# Res_Cut.net
KiCad netlist of a schematic drawn in EAGLE
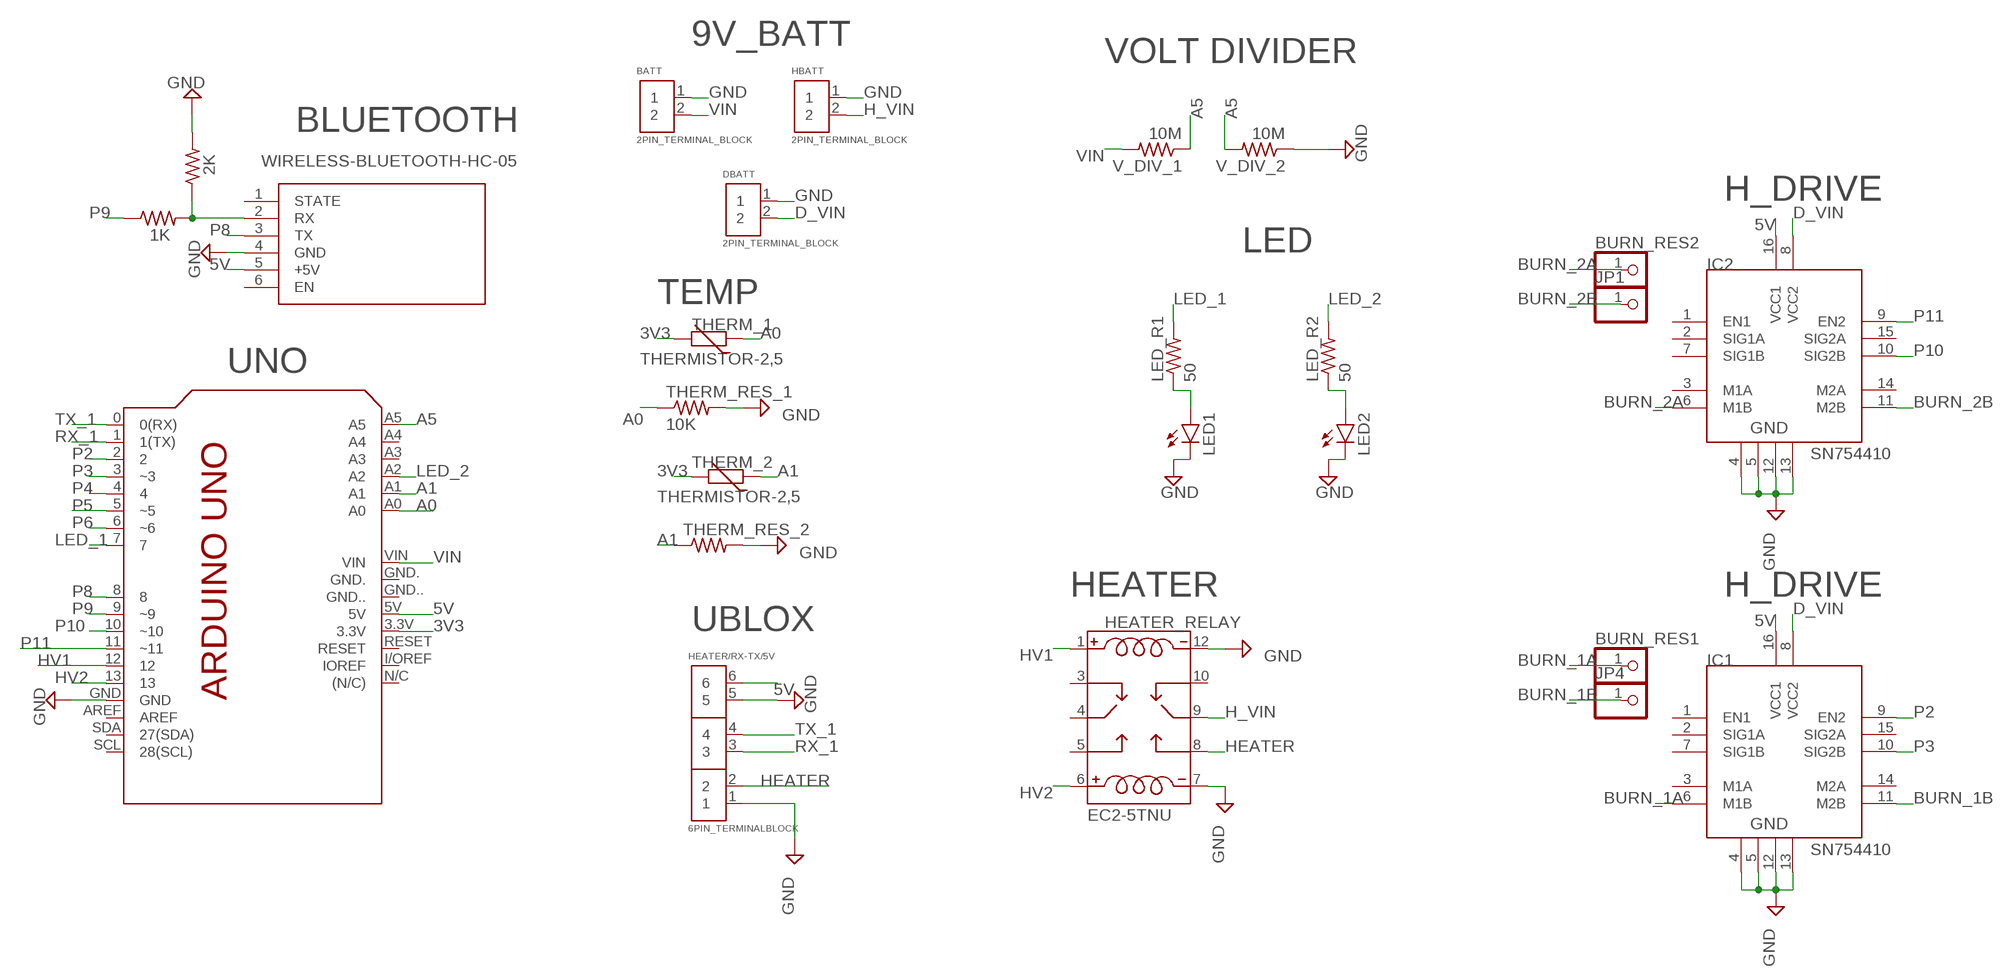
[diagram p0: schematic, sheet 1]

(export (version "E")
  (design (tool "Eeschema 10.0.6"))
  (components
    (comp (ref "BATT")
      (value "2PIN_TERMINAL_BLOCK")
      (footprint "eagle-import:2PIN_TERMINAL_BLOCK")
      (fields
        (field (name "COMMENT") "282834-2")
        (field (name "DIGI-KEY_PART_NUMBER") "A98333-ND")
        (field (name "MF") "TE Connectivity")
      )
      (libsource (lib "eagle-import") (part "2PIN_TERMINAL_BLOCK"))
    )
    (comp (ref "BLUE_R1")
      (value "1K")
      (footprint "eagle-import:0204_7")
      (libsource (lib "eagle-import") (part "R-US_0204/7"))
    )
    (comp (ref "BLUE_R2")
      (value "2K")
      (footprint "eagle-import:0204_7")
      (libsource (lib "eagle-import") (part "R-US_0204/7"))
    )
    (comp (ref "BURN_RES1")
      (value "PINHD-1X1CB")
      (footprint "eagle-import:1X01-CLEANBIG")
      (libsource (lib "eagle-import") (part "PINHD-1X1CB"))
    )
    (comp (ref "BURN_RES2")
      (value "PINHD-1X1CB")
      (footprint "eagle-import:1X01-CLEANBIG")
      (libsource (lib "eagle-import") (part "PINHD-1X1CB"))
    )
    (comp (ref "DBATT")
      (value "2PIN_TERMINAL_BLOCK")
      (footprint "eagle-import:2PIN_TERMINAL_BLOCK")
      (fields
        (field (name "COMMENT") "282834-2")
        (field (name "DIGI-KEY_PART_NUMBER") "A98333-ND")
        (field (name "MF") "TE Connectivity")
      )
      (libsource (lib "eagle-import") (part "2PIN_TERMINAL_BLOCK"))
    )
    (comp (ref "HBATT")
      (value "2PIN_TERMINAL_BLOCK")
      (footprint "eagle-import:2PIN_TERMINAL_BLOCK")
      (fields
        (field (name "COMMENT") "282834-2")
        (field (name "DIGI-KEY_PART_NUMBER") "A98333-ND")
        (field (name "MF") "TE Connectivity")
      )
      (libsource (lib "eagle-import") (part "2PIN_TERMINAL_BLOCK"))
    )
    (comp (ref "HEATER/RX-TX/5V")
      (value "6PIN_TERMINALBLOCK")
      (footprint "eagle-import:6PIN_TERMINALBLOCK")
      (libsource (lib "eagle-import") (part "6PIN_TERMINALBLOCK"))
    )
    (comp (ref "HEATER_RELAY")
      (value "EC2-5TNU")
      (footprint "eagle-import:RELAY_EC2-5TNU")
      (fields (field (name "MF") "KEMET"))
      (libsource (lib "eagle-import") (part "EC2-5TNU"))
    )
    (comp (ref "IC1")
      (value "SN754410")
      (footprint "eagle-import:DIP16")
      (libsource (lib "eagle-import") (part "SN754410"))
    )
    (comp (ref "IC2")
      (value "SN754410")
      (footprint "eagle-import:DIP16")
      (libsource (lib "eagle-import") (part "SN754410"))
    )
    (comp (ref "JP1")
      (value "PINHD-1X1CB")
      (footprint "eagle-import:1X01-CLEANBIG")
      (libsource (lib "eagle-import") (part "PINHD-1X1CB"))
    )
    (comp (ref "JP4")
      (value "PINHD-1X1CB")
      (footprint "eagle-import:1X01-CLEANBIG")
      (libsource (lib "eagle-import") (part "PINHD-1X1CB"))
    )
    (comp (ref "LED1")
      (value "TLLR4400")
      (footprint "eagle-import:LED3MM")
      (fields (field (name "MF") "VISHAY SEMICONDUCTOR"))
      (libsource (lib "eagle-import") (part "TLLR4400"))
    )
    (comp (ref "LED2")
      (value "TLLR4400")
      (footprint "eagle-import:LED3MM")
      (fields (field (name "MF") "VISHAY SEMICONDUCTOR"))
      (libsource (lib "eagle-import") (part "TLLR4400"))
    )
    (comp (ref "LED_R1")
      (value "50")
      (footprint "eagle-import:0204_7")
      (libsource (lib "eagle-import") (part "resistor_348_R-US_0204/7"))
    )
    (comp (ref "LED_R2")
      (value "50")
      (footprint "eagle-import:0204_7")
      (libsource (lib "eagle-import") (part "resistor_348_R-US_0204/7"))
    )
    (comp (ref "PCB1")
      (value "ARDUINO_UNO")
      (footprint "eagle-import:ARDUINO_UNO")
      (libsource (lib "eagle-import") (part "ARDUINO_UNO"))
    )
    (comp (ref "THERM_1")
      (value "THERMISTOR-2,5")
      (footprint "eagle-import:RS-2,5")
      (libsource (lib "eagle-import") (part "THERMISTOR-2,5"))
    )
    (comp (ref "THERM_2")
      (value "THERMISTOR-2,5")
      (footprint "eagle-import:RS-2,5")
      (libsource (lib "eagle-import") (part "THERMISTOR-2,5"))
    )
    (comp (ref "THERM_RES_1")
      (value "10K")
      (footprint "eagle-import:0204_7")
      (libsource (lib "eagle-import") (part "R-US_0204/7"))
    )
    (comp (ref "THERM_RES_2")
      (value "10K")
      (footprint "eagle-import:0204_7")
      (libsource (lib "eagle-import") (part "R-US_0204/7"))
    )
    (comp (ref "U$1")
      (value "WIRELESS-BLUETOOTH-HC-05")
      (footprint "eagle-import:WIRELESS-BLUETOOTH-HC-05")
      (libsource (lib "eagle-import") (part "WIRELESS-BLUETOOTH-HC-05"))
    )
    (comp (ref "V_DIV_1")
      (value "10M")
      (footprint "eagle-import:0204_7")
      (libsource (lib "eagle-import") (part "resistor_348_R-US_0204/7"))
    )
    (comp (ref "V_DIV_2")
      (value "10M")
      (footprint "eagle-import:0204_7")
      (libsource (lib "eagle-import") (part "resistor_348_R-US_0204/7"))
    )
  )
  (nets
    (net (code "1") (name "/3V3") (class "Default")
      (node (ref "PCB1") (pin "3.3V") (pinfunction "3.3V_3.3V") (pintype "bidirectional"))
      (node (ref "THERM_1") (pin "2") (pinfunction "2_2") (pintype "passive"))
      (node (ref "THERM_2") (pin "2") (pinfunction "2_2") (pintype "passive"))
    )
    (net (code "2") (name "/5V") (class "Default")
      (node (ref "HEATER/RX-TX/5V") (pin "6") (pinfunction "6_6") (pintype "passive"))
      (node (ref "IC1") (pin "16") (pinfunction "VCC1_16") (pintype "power_in"))
      (node (ref "IC2") (pin "16") (pinfunction "VCC1_16") (pintype "power_in"))
      (node (ref "PCB1") (pin "5V") (pinfunction "5V_5V") (pintype "bidirectional"))
      (node (ref "U$1") (pin "5") (pinfunction "+5V_5") (pintype "power_in"))
    )
    (net (code "3") (name "/A0") (class "Default")
      (node (ref "PCB1") (pin "A0") (pinfunction "A0_A0") (pintype "bidirectional"))
      (node (ref "THERM_1") (pin "1") (pinfunction "1_1") (pintype "passive"))
      (node (ref "THERM_RES_1") (pin "1") (pinfunction "1_1") (pintype "passive"))
    )
    (net (code "4") (name "/A1") (class "Default")
      (node (ref "PCB1") (pin "A1") (pinfunction "A1_A1") (pintype "bidirectional"))
      (node (ref "THERM_2") (pin "1") (pinfunction "1_1") (pintype "passive"))
      (node (ref "THERM_RES_2") (pin "1") (pinfunction "1_1") (pintype "passive"))
    )
    (net (code "5") (name "/A5") (class "Default")
      (node (ref "PCB1") (pin "A5") (pinfunction "A5_A5") (pintype "bidirectional"))
      (node (ref "V_DIV_1") (pin "1") (pinfunction "1_1") (pintype "passive"))
      (node (ref "V_DIV_2") (pin "2") (pinfunction "2_2") (pintype "passive"))
    )
    (net (code "6") (name "/BURN_1A") (class "Default")
      (node (ref "BURN_RES1") (pin "1") (pinfunction "1_1") (pintype "passive"))
      (node (ref "IC1") (pin "6") (pinfunction "M1B_6") (pintype "bidirectional"))
    )
    (net (code "7") (name "/BURN_1B") (class "Default")
      (node (ref "IC1") (pin "11") (pinfunction "M2B_11") (pintype "bidirectional"))
      (node (ref "JP4") (pin "1") (pinfunction "1_1") (pintype "passive"))
    )
    (net (code "8") (name "/BURN_2A") (class "Default")
      (node (ref "BURN_RES2") (pin "1") (pinfunction "1_1") (pintype "passive"))
      (node (ref "IC2") (pin "6") (pinfunction "M1B_6") (pintype "bidirectional"))
    )
    (net (code "9") (name "/BURN_2B") (class "Default")
      (node (ref "IC2") (pin "11") (pinfunction "M2B_11") (pintype "bidirectional"))
      (node (ref "JP1") (pin "1") (pinfunction "1_1") (pintype "passive"))
    )
    (net (code "10") (name "/D_VIN") (class "Default")
      (node (ref "DBATT") (pin "2") (pinfunction "2_2") (pintype "passive"))
      (node (ref "IC1") (pin "8") (pinfunction "VCC2_8") (pintype "power_in"))
      (node (ref "IC2") (pin "8") (pinfunction "VCC2_8") (pintype "power_in"))
    )
    (net (code "11") (name "/HEATER") (class "Default")
      (node (ref "HEATER/RX-TX/5V") (pin "2") (pinfunction "2_2") (pintype "passive"))
      (node (ref "HEATER_RELAY") (pin "8") (pinfunction "NO_8") (pintype "passive"))
    )
    (net (code "12") (name "/HV1") (class "Default")
      (node (ref "HEATER_RELAY") (pin "1") (pinfunction "C1_1") (pintype "passive"))
      (node (ref "PCB1") (pin "12") (pinfunction "12_12") (pintype "bidirectional"))
    )
    (net (code "13") (name "/HV2") (class "Default")
      (node (ref "HEATER_RELAY") (pin "6") (pinfunction "C3_6") (pintype "passive"))
      (node (ref "PCB1") (pin "13") (pinfunction "13_13") (pintype "bidirectional"))
    )
    (net (code "14") (name "/H_VIN") (class "Default")
      (node (ref "HBATT") (pin "2") (pinfunction "2_2") (pintype "passive"))
      (node (ref "HEATER_RELAY") (pin "9") (pinfunction "M_9") (pintype "passive"))
    )
    (net (code "15") (name "/LED_1") (class "Default")
      (node (ref "LED_R1") (pin "2") (pinfunction "2_2") (pintype "passive"))
      (node (ref "PCB1") (pin "7") (pinfunction "7_7") (pintype "bidirectional"))
    )
    (net (code "16") (name "/LED_2") (class "Default")
      (node (ref "LED_R2") (pin "2") (pinfunction "2_2") (pintype "passive"))
      (node (ref "PCB1") (pin "A2") (pinfunction "A2_A2") (pintype "bidirectional"))
    )
    (net (code "17") (name "/P2") (class "Default")
      (node (ref "IC1") (pin "9") (pinfunction "EN2_9") (pintype "bidirectional"))
      (node (ref "PCB1") (pin "2") (pinfunction "2_2") (pintype "bidirectional"))
    )
    (net (code "18") (name "/P3") (class "Default")
      (node (ref "IC1") (pin "10") (pinfunction "SIG2B_10") (pintype "bidirectional"))
      (node (ref "PCB1") (pin "3") (pinfunction "~{3}_3") (pintype "bidirectional"))
    )
    (net (code "19") (name "/P4") (class "Default")
      (node (ref "PCB1") (pin "4") (pinfunction "4_4") (pintype "bidirectional"))
    )
    (net (code "20") (name "/P5") (class "Default")
      (node (ref "PCB1") (pin "5") (pinfunction "~{5}_5") (pintype "bidirectional"))
    )
    (net (code "21") (name "/P6") (class "Default")
      (node (ref "PCB1") (pin "6") (pinfunction "~{6}_6") (pintype "bidirectional"))
    )
    (net (code "22") (name "/P8") (class "Default")
      (node (ref "PCB1") (pin "8") (pinfunction "8_8") (pintype "bidirectional"))
      (node (ref "U$1") (pin "3") (pinfunction "TX_3") (pintype "bidirectional"))
    )
    (net (code "23") (name "/P9") (class "Default")
      (node (ref "BLUE_R1") (pin "1") (pinfunction "1_1") (pintype "passive"))
      (node (ref "PCB1") (pin "9") (pinfunction "~{9}_9") (pintype "bidirectional"))
    )
    (net (code "24") (name "/P10") (class "Default")
      (node (ref "IC2") (pin "10") (pinfunction "SIG2B_10") (pintype "bidirectional"))
      (node (ref "PCB1") (pin "10") (pinfunction "~{10}_10") (pintype "bidirectional"))
    )
    (net (code "25") (name "/P11") (class "Default")
      (node (ref "IC2") (pin "9") (pinfunction "EN2_9") (pintype "bidirectional"))
      (node (ref "PCB1") (pin "11") (pinfunction "~{11}_11") (pintype "bidirectional"))
    )
    (net (code "26") (name "/RX_1") (class "Default")
      (node (ref "HEATER/RX-TX/5V") (pin "3") (pinfunction "3_3") (pintype "passive"))
      (node (ref "PCB1") (pin "1") (pinfunction "1(TX)_1") (pintype "bidirectional"))
    )
    (net (code "27") (name "/TX_1") (class "Default")
      (node (ref "HEATER/RX-TX/5V") (pin "4") (pinfunction "4_4") (pintype "passive"))
      (node (ref "PCB1") (pin "0") (pinfunction "0(RX)_0") (pintype "bidirectional"))
    )
    (net (code "28") (name "/VIN") (class "Default")
      (node (ref "BATT") (pin "2") (pinfunction "2_2") (pintype "passive"))
      (node (ref "PCB1") (pin "VIN") (pinfunction "VIN_VIN") (pintype "bidirectional"))
      (node (ref "V_DIV_1") (pin "2") (pinfunction "2_2") (pintype "passive"))
    )
    (net (code "29") (name "GND") (class "Default")
      (node (ref "BATT") (pin "1") (pinfunction "1_1") (pintype "passive"))
      (node (ref "BLUE_R2") (pin "2") (pinfunction "2_2") (pintype "passive"))
      (node (ref "DBATT") (pin "1") (pinfunction "1_1") (pintype "passive"))
      (node (ref "HBATT") (pin "1") (pinfunction "1_1") (pintype "passive"))
      (node (ref "HEATER/RX-TX/5V") (pin "1") (pinfunction "1_1") (pintype "passive"))
      (node (ref "HEATER/RX-TX/5V") (pin "5") (pinfunction "5_5") (pintype "passive"))
      (node (ref "HEATER_RELAY") (pin "12") (pinfunction "C2_12") (pintype "passive"))
      (node (ref "HEATER_RELAY") (pin "7") (pinfunction "C4_7") (pintype "passive"))
      (node (ref "IC1") (pin "12") (pinfunction "P12_12") (pintype "power_in"))
      (node (ref "IC1") (pin "13") (pinfunction "P13_13") (pintype "power_in"))
      (node (ref "IC1") (pin "4") (pinfunction "P4_4") (pintype "power_in"))
      (node (ref "IC1") (pin "5") (pinfunction "P5_5") (pintype "power_in"))
      (node (ref "IC2") (pin "12") (pinfunction "P12_12") (pintype "power_in"))
      (node (ref "IC2") (pin "13") (pinfunction "P13_13") (pintype "power_in"))
      (node (ref "IC2") (pin "4") (pinfunction "P4_4") (pintype "power_in"))
      (node (ref "IC2") (pin "5") (pinfunction "P5_5") (pintype "power_in"))
      (node (ref "LED1") (pin "K") (pinfunction "C_K") (pintype "passive"))
      (node (ref "LED2") (pin "K") (pinfunction "C_K") (pintype "passive"))
      (node (ref "PCB1") (pin "GND") (pinfunction "GND_GND") (pintype "bidirectional"))
      (node (ref "THERM_RES_1") (pin "2") (pinfunction "2_2") (pintype "passive"))
      (node (ref "THERM_RES_2") (pin "2") (pinfunction "2_2") (pintype "passive"))
      (node (ref "U$1") (pin "4") (pinfunction "GND_4") (pintype "power_in"))
      (node (ref "V_DIV_2") (pin "1") (pinfunction "1_1") (pintype "passive"))
    )
    (net (code "30") (name "Net-(LED1-PadA)") (class "Default")
      (node (ref "LED1") (pin "A") (pinfunction "A_A") (pintype "passive"))
      (node (ref "LED_R1") (pin "1") (pinfunction "1_1") (pintype "passive"))
    )
    (net (code "31") (name "Net-(LED2-PadA)") (class "Default")
      (node (ref "LED2") (pin "A") (pinfunction "A_A") (pintype "passive"))
      (node (ref "LED_R2") (pin "1") (pinfunction "1_1") (pintype "passive"))
    )
    (net (code "32") (name "Net-(U$1-RX)") (class "Default")
      (node (ref "BLUE_R1") (pin "2") (pinfunction "2_2") (pintype "passive"))
      (node (ref "BLUE_R2") (pin "1") (pinfunction "1_1") (pintype "passive"))
      (node (ref "U$1") (pin "2") (pinfunction "RX_2") (pintype "bidirectional"))
    )
    (net (code "33") (name "unconnected-(HEATER_RELAY-M1-Pad4)") (class "Default")
      (node (ref "HEATER_RELAY") (pin "4") (pinfunction "M1_4") (pintype "passive"))
    )
    (net (code "34") (name "unconnected-(HEATER_RELAY-NC-Pad10)") (class "Default")
      (node (ref "HEATER_RELAY") (pin "10") (pinfunction "NC_10") (pintype "passive"))
    )
    (net (code "35") (name "unconnected-(HEATER_RELAY-NC1-Pad3)") (class "Default")
      (node (ref "HEATER_RELAY") (pin "3") (pinfunction "NC1_3") (pintype "passive"))
    )
    (net (code "36") (name "unconnected-(HEATER_RELAY-NO1-Pad5)") (class "Default")
      (node (ref "HEATER_RELAY") (pin "5") (pinfunction "NO1_5") (pintype "passive"))
    )
    (net (code "37") (name "unconnected-(IC1-EN1-Pad1)") (class "Default")
      (node (ref "IC1") (pin "1") (pinfunction "EN1_1") (pintype "bidirectional"))
    )
    (net (code "38") (name "unconnected-(IC1-M1A-Pad3)") (class "Default")
      (node (ref "IC1") (pin "3") (pinfunction "M1A_3") (pintype "bidirectional"))
    )
    (net (code "39") (name "unconnected-(IC1-M2A-Pad14)") (class "Default")
      (node (ref "IC1") (pin "14") (pinfunction "M2A_14") (pintype "bidirectional"))
    )
    (net (code "40") (name "unconnected-(IC1-SIG1A-Pad2)") (class "Default")
      (node (ref "IC1") (pin "2") (pinfunction "SIG1A_2") (pintype "bidirectional"))
    )
    (net (code "41") (name "unconnected-(IC1-SIG1B-Pad7)") (class "Default")
      (node (ref "IC1") (pin "7") (pinfunction "SIG1B_7") (pintype "bidirectional"))
    )
    (net (code "42") (name "unconnected-(IC1-SIG2A-Pad15)") (class "Default")
      (node (ref "IC1") (pin "15") (pinfunction "SIG2A_15") (pintype "bidirectional"))
    )
    (net (code "43") (name "unconnected-(IC2-EN1-Pad1)") (class "Default")
      (node (ref "IC2") (pin "1") (pinfunction "EN1_1") (pintype "bidirectional"))
    )
    (net (code "44") (name "unconnected-(IC2-M1A-Pad3)") (class "Default")
      (node (ref "IC2") (pin "3") (pinfunction "M1A_3") (pintype "bidirectional"))
    )
    (net (code "45") (name "unconnected-(IC2-M2A-Pad14)") (class "Default")
      (node (ref "IC2") (pin "14") (pinfunction "M2A_14") (pintype "bidirectional"))
    )
    (net (code "46") (name "unconnected-(IC2-SIG1A-Pad2)") (class "Default")
      (node (ref "IC2") (pin "2") (pinfunction "SIG1A_2") (pintype "bidirectional"))
    )
    (net (code "47") (name "unconnected-(IC2-SIG1B-Pad7)") (class "Default")
      (node (ref "IC2") (pin "7") (pinfunction "SIG1B_7") (pintype "bidirectional"))
    )
    (net (code "48") (name "unconnected-(IC2-SIG2A-Pad15)") (class "Default")
      (node (ref "IC2") (pin "15") (pinfunction "SIG2A_15") (pintype "bidirectional"))
    )
    (net (code "49") (name "unconnected-(PCB1-(N{slash}C)-PadN{slash}C)") (class "Default")
      (node (ref "PCB1") (pin "N/C") (pinfunction "(N/C)_N/C") (pintype "bidirectional"))
    )
    (net (code "50") (name "unconnected-(PCB1-27(SDA)-PadSDA)") (class "Default")
      (node (ref "PCB1") (pin "SDA") (pinfunction "27(SDA)_SDA") (pintype "bidirectional"))
    )
    (net (code "51") (name "unconnected-(PCB1-28(SCL)-PadSCL)") (class "Default")
      (node (ref "PCB1") (pin "SCL") (pinfunction "28(SCL)_SCL") (pintype "bidirectional"))
    )
    (net (code "52") (name "unconnected-(PCB1-IOREF-PadI{slash}OREF)") (class "Default")
      (node (ref "PCB1") (pin "I/OREF") (pinfunction "IOREF_I/OREF") (pintype "bidirectional"))
    )
    (net (code "53") (name "unconnected-(PCB1-PadA3)") (class "Default")
      (node (ref "PCB1") (pin "A3") (pinfunction "A3_A3") (pintype "bidirectional"))
    )
    (net (code "54") (name "unconnected-(PCB1-PadA4)") (class "Default")
      (node (ref "PCB1") (pin "A4") (pinfunction "A4_A4") (pintype "bidirectional"))
    )
    (net (code "55") (name "unconnected-(PCB1-PadAREF)") (class "Default")
      (node (ref "PCB1") (pin "AREF") (pinfunction "AREF_AREF") (pintype "bidirectional"))
    )
    (net (code "56") (name "unconnected-(PCB1-PadGND.)") (class "Default")
      (node (ref "PCB1") (pin "GND.") (pinfunction "GND._GND.") (pintype "bidirectional"))
    )
    (net (code "57") (name "unconnected-(PCB1-PadGND..)") (class "Default")
      (node (ref "PCB1") (pin "GND..") (pinfunction "GND.._GND..") (pintype "bidirectional"))
    )
    (net (code "58") (name "unconnected-(PCB1-PadRESET)") (class "Default")
      (node (ref "PCB1") (pin "RESET") (pinfunction "RESET_RESET") (pintype "bidirectional"))
    )
    (net (code "59") (name "unconnected-(U$1-EN-Pad6)") (class "Default")
      (node (ref "U$1") (pin "6") (pinfunction "EN_6") (pintype "bidirectional"))
    )
    (net (code "60") (name "unconnected-(U$1-STATE-Pad1)") (class "Default")
      (node (ref "U$1") (pin "1") (pinfunction "STATE_1") (pintype "bidirectional"))
    )
  )
)
